# PWM.net
KiCad netlist of a schematic drawn in Altium Designer
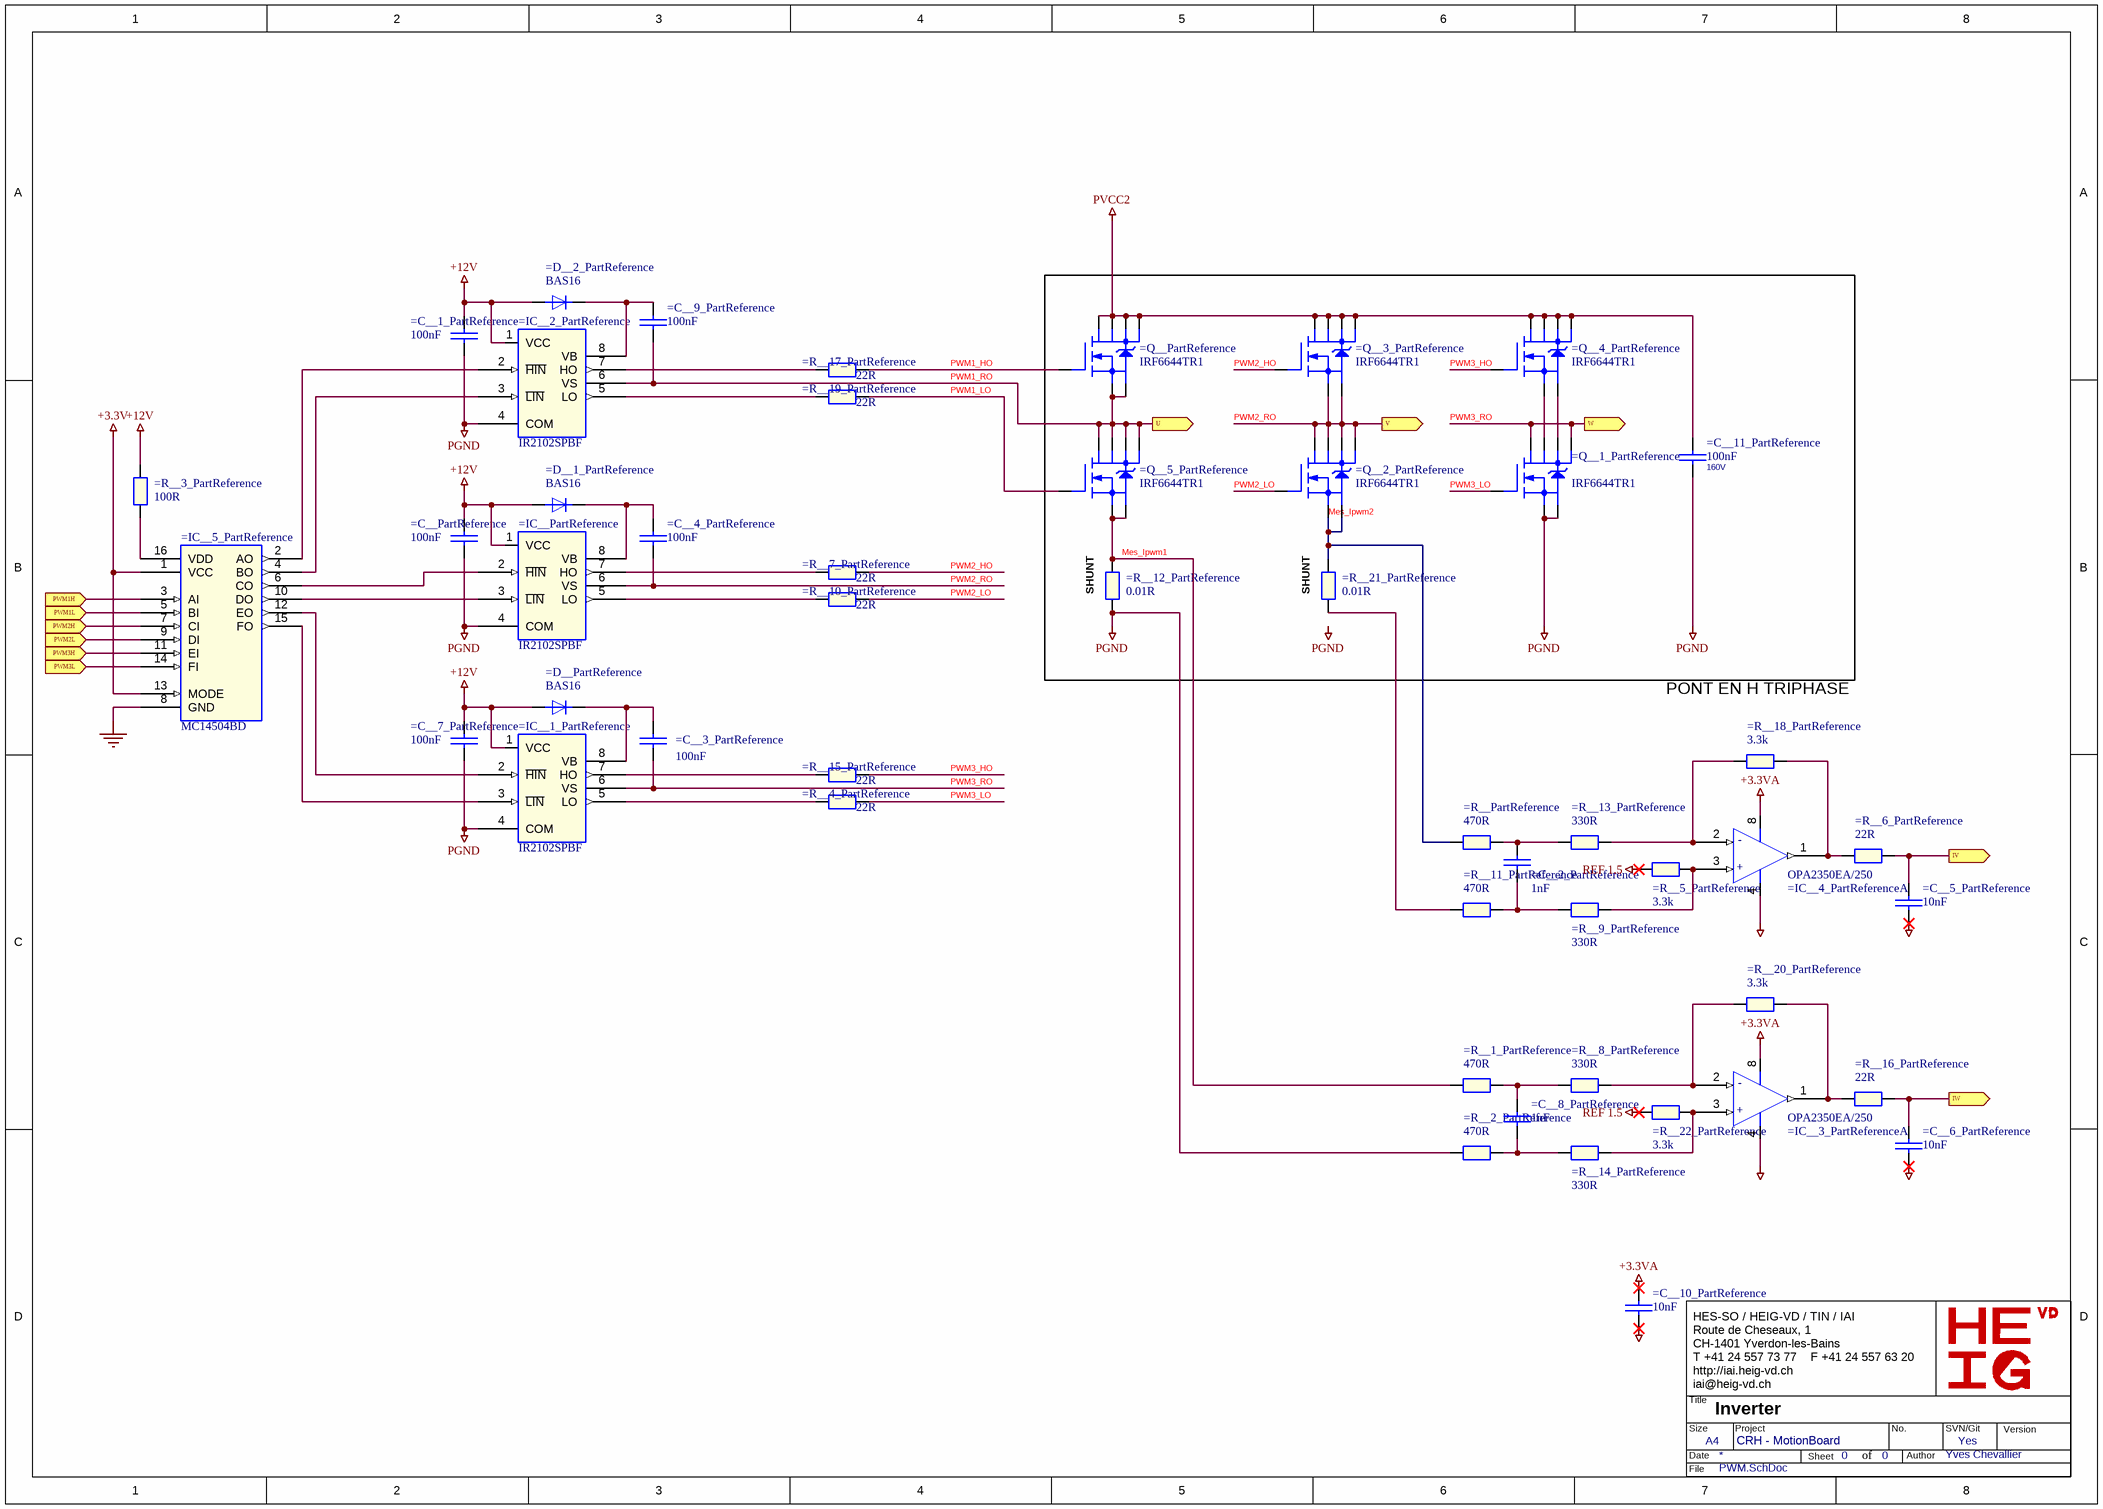
[diagram p0: PWM.SchDoc]

(export (version "E")
  (design (tool "Eeschema 10.0.6"))
  (components
    (comp (ref "=C__1_PartReference")
      (value "100nF")
      (footprint "SM/C_0805")
      (libsource (lib "*") (part "C_Dup1"))
    )
    (comp (ref "=C__2_PartReference")
      (value "1nF")
      (footprint "SM/C_0805")
      (libsource (lib "*") (part "C_Dup1"))
    )
    (comp (ref "=C__3_PartReference")
      (value "100nF")
      (footprint "SM/C_0805")
      (libsource (lib "*") (part "C_Dup1"))
    )
    (comp (ref "=C__4_PartReference")
      (value "100nF")
      (footprint "SM/C_0805")
      (libsource (lib "*") (part "C_Dup1"))
    )
    (comp (ref "=C__5_PartReference")
      (value "10nF")
      (footprint "SM/C_0805")
      (libsource (lib "*") (part "C_Dup1"))
    )
    (comp (ref "=C__6_PartReference")
      (value "10nF")
      (footprint "SM/C_0805")
      (libsource (lib "*") (part "C_Dup1"))
    )
    (comp (ref "=C__7_PartReference")
      (value "100nF")
      (footprint "SM/C_0805")
      (libsource (lib "*") (part "C_Dup1"))
    )
    (comp (ref "=C__8_PartReference")
      (value "1nF")
      (footprint "SM/C_0805")
      (libsource (lib "*") (part "C_Dup1"))
    )
    (comp (ref "=C__9_PartReference")
      (value "100nF")
      (footprint "SM/C_0805")
      (libsource (lib "*") (part "C_Dup1"))
    )
    (comp (ref "=C__10_PartReference")
      (value "10nF")
      (footprint "SM/C_0805")
      (libsource (lib "*") (part "C_Dup1"))
    )
    (comp (ref "=C__11_PartReference")
      (value "100nF")
      (footprint "SM/C_0805")
      (fields (field (name "VOLTAGE") "160V"))
      (libsource (lib "*") (part "C_Dup1"))
    )
    (comp (ref "=C__PartReference")
      (value "100nF")
      (footprint "SM/C_0805")
      (libsource (lib "*") (part "C_Dup1"))
    )
    (comp (ref "=D__1_PartReference")
      (value "BAS16")
      (footprint "HEIG/SM/SOT23")
      (fields (field (name "VOLTAGE") "85V"))
      (libsource (lib "*") (part "D_2"))
    )
    (comp (ref "=D__2_PartReference")
      (value "BAS16")
      (footprint "HEIG/SM/SOT23")
      (fields (field (name "VOLTAGE") "85V"))
      (libsource (lib "*") (part "D_4"))
    )
    (comp (ref "=D__PartReference")
      (value "BAS16")
      (footprint "HEIG/SM/SOT23")
      (fields (field (name "VOLTAGE") "85V"))
      (libsource (lib "*") (part "D_3"))
    )
    (comp (ref "=IC__1_PartReference")
      (value "IR2102SPBF")
      (footprint "SOG.050/8/WG.244/L.200")
      (libsource (lib "*") (part "IR2102/SO_0"))
    )
    (comp (ref "=IC__2_PartReference")
      (value "IR2102SPBF")
      (footprint "SOG.050/8/WG.244/L.200")
      (libsource (lib "*") (part "IR2102/SO_0"))
    )
    (comp (ref "=IC__3_PartReference")
      (value "OPA2350EA/250")
      (footprint "HEIG/SM/MSOP8")
      (libsource (lib "*") (part "OPA2340_2"))
    )
    (comp (ref "=IC__4_PartReference")
      (value "OPA2350EA/250")
      (footprint "HEIG/SM/MSOP8")
      (libsource (lib "*") (part "OPA2340_2"))
    )
    (comp (ref "=IC__5_PartReference")
      (value "MC14504BD")
      (footprint "SOG.050/16/WG.244/L.400")
      (libsource (lib "*") (part "CD4504BMS_1"))
    )
    (comp (ref "=IC__PartReference")
      (value "IR2102SPBF")
      (footprint "SOG.050/8/WG.244/L.200")
      (libsource (lib "*") (part "IR2102/SO_0_Dup1"))
    )
    (comp (ref "=Q__1_PartReference")
      (value "IRF6644TR1")
      (footprint "HEIG/DIRECTFET/MN")
      (libsource (lib "*") (part "IRF3710S/SM_0"))
    )
    (comp (ref "=Q__2_PartReference")
      (value "IRF6644TR1")
      (footprint "HEIG/DIRECTFET/MN")
      (libsource (lib "*") (part "IRF3710S/SM_0"))
    )
    (comp (ref "=Q__3_PartReference")
      (value "IRF6644TR1")
      (footprint "HEIG/DIRECTFET/MN")
      (libsource (lib "*") (part "IRF3710S/SM_0"))
    )
    (comp (ref "=Q__4_PartReference")
      (value "IRF6644TR1")
      (footprint "HEIG/DIRECTFET/MN")
      (libsource (lib "*") (part "IRF3710S/SM_0"))
    )
    (comp (ref "=Q__5_PartReference")
      (value "IRF6644TR1")
      (footprint "HEIG/DIRECTFET/MN")
      (libsource (lib "*") (part "IRF3710S/SM_0"))
    )
    (comp (ref "=Q__PartReference")
      (value "IRF6644TR1")
      (footprint "HEIG/DIRECTFET/MN")
      (libsource (lib "*") (part "IRF3710S/SM_0"))
    )
    (comp (ref "=R__1_PartReference") (value "470R") (footprint "R400") (libsource (lib "*") (part "R_Dup1")))
    (comp (ref "=R__2_PartReference") (value "470R") (footprint "R400") (libsource (lib "*") (part "R_Dup1")))
    (comp (ref "=R__3_PartReference")
      (value "100R")
      (footprint "R400")
      (libsource (lib "") (part "R_Dup1_1"))
    )
    (comp (ref "=R__4_PartReference") (value "22R") (footprint "R400") (libsource (lib "*") (part "R_Dup1")))
    (comp (ref "=R__5_PartReference") (value "3.3k") (footprint "R400") (libsource (lib "*") (part "R_Dup1")))
    (comp (ref "=R__6_PartReference") (value "22R") (footprint "R400") (libsource (lib "*") (part "R_Dup1")))
    (comp (ref "=R__7_PartReference") (value "22R") (footprint "R400") (libsource (lib "*") (part "R_Dup1")))
    (comp (ref "=R__8_PartReference") (value "330R") (footprint "R400") (libsource (lib "*") (part "R_Dup1")))
    (comp (ref "=R__9_PartReference") (value "330R") (footprint "R400") (libsource (lib "*") (part "R_Dup1")))
    (comp (ref "=R__10_PartReference") (value "22R") (footprint "R400") (libsource (lib "*") (part "R_Dup1")))
    (comp (ref "=R__11_PartReference")
      (value "470R")
      (footprint "R400")
      (libsource (lib "*") (part "R_Dup1"))
    )
    (comp (ref "=R__12_PartReference")
      (value "0.01R")
      (footprint "R400")
      (fields (field (name "VOLTAGE") "200V"))
      (libsource (lib "") (part "R_Dup1_2"))
    )
    (comp (ref "=R__13_PartReference")
      (value "330R")
      (footprint "R400")
      (libsource (lib "*") (part "R_Dup1"))
    )
    (comp (ref "=R__14_PartReference")
      (value "330R")
      (footprint "R400")
      (libsource (lib "*") (part "R_Dup1"))
    )
    (comp (ref "=R__15_PartReference") (value "22R") (footprint "R400") (libsource (lib "*") (part "R_Dup1")))
    (comp (ref "=R__16_PartReference") (value "22R") (footprint "R400") (libsource (lib "*") (part "R_Dup1")))
    (comp (ref "=R__17_PartReference") (value "22R") (footprint "R400") (libsource (lib "*") (part "R_Dup1")))
    (comp (ref "=R__18_PartReference")
      (value "3.3k")
      (footprint "R400")
      (libsource (lib "*") (part "R_Dup1"))
    )
    (comp (ref "=R__19_PartReference") (value "22R") (footprint "R400") (libsource (lib "*") (part "R_Dup1")))
    (comp (ref "=R__20_PartReference")
      (value "3.3k")
      (footprint "R400")
      (libsource (lib "*") (part "R_Dup1"))
    )
    (comp (ref "=R__21_PartReference")
      (value "0.01R")
      (footprint "R400")
      (fields (field (name "VOLTAGE") "200V"))
      (libsource (lib "") (part "R_Dup1_2"))
    )
    (comp (ref "=R__22_PartReference")
      (value "3.3k")
      (footprint "R400")
      (libsource (lib "*") (part "R_Dup1"))
    )
    (comp (ref "=R__PartReference") (value "470R") (footprint "R400") (libsource (lib "*") (part "R_Dup1")))
  )
  (nets
    (net (code "1") (name "+3.3V") (class "Default")
      (node (ref "=IC__5_PartReference") (pin "1") (pinfunction "VCC_1") (pintype "power_in"))
      (node (ref "=IC__5_PartReference") (pin "13") (pinfunction "MODE_13") (pintype "input"))
    )
    (net (code "2") (name "+3.3VA") (class "Default")
      (node (ref "=C__10_PartReference") (pin "1") (pinfunction "1_1") (pintype "passive"))
      (node (ref "=IC__3_PartReference") (pin "8") (pinfunction "+VCC_8") (pintype "power_in"))
      (node (ref "=IC__4_PartReference") (pin "8") (pinfunction "+VCC_8") (pintype "power_in"))
    )
    (net (code "3") (name "+12V") (class "Default")
      (node (ref "=C__1_PartReference") (pin "1") (pinfunction "1_1") (pintype "passive"))
      (node (ref "=C__7_PartReference") (pin "1") (pinfunction "1_1") (pintype "passive"))
      (node (ref "=C__PartReference") (pin "1") (pinfunction "1_1") (pintype "passive"))
      (node (ref "=D__1_PartReference") (pin "1") (pinfunction "a_1") (pintype "passive"))
      (node (ref "=D__2_PartReference") (pin "1") (pinfunction "a_1") (pintype "passive"))
      (node (ref "=D__PartReference") (pin "1") (pinfunction "a_1") (pintype "passive"))
      (node (ref "=IC__1_PartReference") (pin "1") (pinfunction "VCC_1") (pintype "power_in"))
      (node (ref "=IC__2_PartReference") (pin "1") (pinfunction "VCC_1") (pintype "power_in"))
      (node (ref "=IC__PartReference") (pin "1") (pinfunction "VCC_1") (pintype "power_in"))
      (node (ref "=R__3_PartReference") (pin "2") (pinfunction "2_2") (pintype "passive"))
    )
    (net (code "4") (name "/IV") (class "Default")
      (node (ref "=C__5_PartReference") (pin "1") (pinfunction "1_1") (pintype "passive"))
      (node (ref "=R__6_PartReference") (pin "2") (pinfunction "2_2") (pintype "passive"))
    )
    (net (code "5") (name "/IW") (class "Default")
      (node (ref "=C__6_PartReference") (pin "1") (pinfunction "1_1") (pintype "passive"))
      (node (ref "=R__16_PartReference") (pin "2") (pinfunction "2_2") (pintype "passive"))
    )
    (net (code "6") (name "/Mes_Ipwm1") (class "Default")
      (node (ref "=Q__5_PartReference") (pin "S1") (pinfunction "S_S1") (pintype "passive"))
      (node (ref "=Q__5_PartReference") (pin "S2") (pinfunction "S_S2") (pintype "passive"))
      (node (ref "=R__12_PartReference") (pin "1") (pinfunction "1_1") (pintype "passive"))
      (node (ref "=R__1_PartReference") (pin "1") (pinfunction "1_1") (pintype "passive"))
    )
    (net (code "7") (name "/Mes_Ipwm2") (class "Default")
      (node (ref "=Q__2_PartReference") (pin "S1") (pinfunction "S_S1") (pintype "passive"))
      (node (ref "=Q__2_PartReference") (pin "S2") (pinfunction "S_S2") (pintype "passive"))
      (node (ref "=R__21_PartReference") (pin "1") (pinfunction "1_1") (pintype "passive"))
      (node (ref "=R__PartReference") (pin "1") (pinfunction "1_1") (pintype "passive"))
    )
    (net (code "8") (name "/PWM1H") (class "Default")
      (node (ref "=IC__5_PartReference") (pin "3") (pinfunction "AI_3") (pintype "input"))
    )
    (net (code "9") (name "/PWM1L") (class "Default")
      (node (ref "=IC__5_PartReference") (pin "5") (pinfunction "BI_5") (pintype "input"))
    )
    (net (code "10") (name "/PWM1_HO") (class "Default")
      (node (ref "=Q__PartReference") (pin "G") (pinfunction "G_G") (pintype "passive"))
      (node (ref "=R__17_PartReference") (pin "2") (pinfunction "2_2") (pintype "passive"))
    )
    (net (code "11") (name "/PWM1_LO") (class "Default")
      (node (ref "=Q__5_PartReference") (pin "G") (pinfunction "G_G") (pintype "passive"))
      (node (ref "=R__19_PartReference") (pin "2") (pinfunction "2_2") (pintype "passive"))
    )
    (net (code "12") (name "/PWM1_RO") (class "Default")
      (node (ref "=C__9_PartReference") (pin "2") (pinfunction "2_2") (pintype "passive"))
      (node (ref "=IC__2_PartReference") (pin "6") (pinfunction "VS_6") (pintype "passive"))
      (node (ref "=Q__5_PartReference") (pin "D1") (pinfunction "D_D1") (pintype "passive"))
      (node (ref "=Q__5_PartReference") (pin "D2") (pinfunction "D_D2") (pintype "passive"))
      (node (ref "=Q__5_PartReference") (pin "D3") (pinfunction "D_D3") (pintype "passive"))
      (node (ref "=Q__5_PartReference") (pin "D4") (pinfunction "D_D4") (pintype "passive"))
      (node (ref "=Q__PartReference") (pin "S1") (pinfunction "S_S1") (pintype "passive"))
      (node (ref "=Q__PartReference") (pin "S2") (pinfunction "S_S2") (pintype "passive"))
    )
    (net (code "13") (name "/PWM2H") (class "Default")
      (node (ref "=IC__5_PartReference") (pin "7") (pinfunction "CI_7") (pintype "input"))
    )
    (net (code "14") (name "/PWM2L") (class "Default")
      (node (ref "=IC__5_PartReference") (pin "9") (pinfunction "DI_9") (pintype "input"))
    )
    (net (code "15") (name "/PWM2_HO") (class "Default")
      (node (ref "=Q__3_PartReference") (pin "G") (pinfunction "G_G") (pintype "passive"))
      (node (ref "=R__7_PartReference") (pin "2") (pinfunction "2_2") (pintype "passive"))
    )
    (net (code "16") (name "/PWM2_LO") (class "Default")
      (node (ref "=Q__2_PartReference") (pin "G") (pinfunction "G_G") (pintype "passive"))
      (node (ref "=R__10_PartReference") (pin "2") (pinfunction "2_2") (pintype "passive"))
    )
    (net (code "17") (name "/PWM2_RO") (class "Default")
      (node (ref "=C__4_PartReference") (pin "2") (pinfunction "2_2") (pintype "passive"))
      (node (ref "=IC__PartReference") (pin "6") (pinfunction "VS_6") (pintype "passive"))
      (node (ref "=Q__2_PartReference") (pin "D1") (pinfunction "D_D1") (pintype "passive"))
      (node (ref "=Q__2_PartReference") (pin "D2") (pinfunction "D_D2") (pintype "passive"))
      (node (ref "=Q__2_PartReference") (pin "D3") (pinfunction "D_D3") (pintype "passive"))
      (node (ref "=Q__2_PartReference") (pin "D4") (pinfunction "D_D4") (pintype "passive"))
      (node (ref "=Q__3_PartReference") (pin "S1") (pinfunction "S_S1") (pintype "passive"))
      (node (ref "=Q__3_PartReference") (pin "S2") (pinfunction "S_S2") (pintype "passive"))
    )
    (net (code "18") (name "/PWM3H") (class "Default")
      (node (ref "=IC__5_PartReference") (pin "11") (pinfunction "EI_11") (pintype "input"))
    )
    (net (code "19") (name "/PWM3L") (class "Default")
      (node (ref "=IC__5_PartReference") (pin "14") (pinfunction "FI_14") (pintype "input"))
    )
    (net (code "20") (name "/PWM3_HO") (class "Default")
      (node (ref "=Q__4_PartReference") (pin "G") (pinfunction "G_G") (pintype "passive"))
      (node (ref "=R__15_PartReference") (pin "2") (pinfunction "2_2") (pintype "passive"))
    )
    (net (code "21") (name "/PWM3_LO") (class "Default")
      (node (ref "=Q__1_PartReference") (pin "G") (pinfunction "G_G") (pintype "passive"))
      (node (ref "=R__4_PartReference") (pin "2") (pinfunction "2_2") (pintype "passive"))
    )
    (net (code "22") (name "/PWM3_RO") (class "Default")
      (node (ref "=C__3_PartReference") (pin "2") (pinfunction "2_2") (pintype "passive"))
      (node (ref "=IC__1_PartReference") (pin "6") (pinfunction "VS_6") (pintype "passive"))
      (node (ref "=Q__1_PartReference") (pin "D3") (pinfunction "D_D3") (pintype "passive"))
      (node (ref "=Q__1_PartReference") (pin "D4") (pinfunction "D_D4") (pintype "passive"))
    )
    (net (code "23") (name "AGND") (class "Default")
      (node (ref "=C__10_PartReference") (pin "2") (pinfunction "2_2") (pintype "passive"))
      (node (ref "=C__5_PartReference") (pin "2") (pinfunction "2_2") (pintype "passive"))
      (node (ref "=C__6_PartReference") (pin "2") (pinfunction "2_2") (pintype "passive"))
      (node (ref "=IC__3_PartReference") (pin "4") (pinfunction "-VCC_4") (pintype "power_in"))
      (node (ref "=IC__4_PartReference") (pin "4") (pinfunction "-VCC_4") (pintype "power_in"))
    )
    (net (code "24") (name "GND") (class "Default")
      (node (ref "=IC__5_PartReference") (pin "8") (pinfunction "GND_8") (pintype "power_in"))
    )
    (net (code "25") (name "Net-(=C__2_PartReference-Pad1)") (class "Default")
      (node (ref "=C__2_PartReference") (pin "1") (pinfunction "1_1") (pintype "passive"))
      (node (ref "=R__13_PartReference") (pin "1") (pinfunction "1_1") (pintype "passive"))
      (node (ref "=R__PartReference") (pin "2") (pinfunction "2_2") (pintype "passive"))
    )
    (net (code "26") (name "Net-(=C__2_PartReference-Pad2)") (class "Default")
      (node (ref "=C__2_PartReference") (pin "2") (pinfunction "2_2") (pintype "passive"))
      (node (ref "=R__11_PartReference") (pin "2") (pinfunction "2_2") (pintype "passive"))
      (node (ref "=R__9_PartReference") (pin "1") (pinfunction "1_1") (pintype "passive"))
    )
    (net (code "27") (name "Net-(=C__8_PartReference-Pad1)") (class "Default")
      (node (ref "=C__8_PartReference") (pin "1") (pinfunction "1_1") (pintype "passive"))
      (node (ref "=R__1_PartReference") (pin "2") (pinfunction "2_2") (pintype "passive"))
      (node (ref "=R__8_PartReference") (pin "1") (pinfunction "1_1") (pintype "passive"))
    )
    (net (code "28") (name "Net-(=C__8_PartReference-Pad2)") (class "Default")
      (node (ref "=C__8_PartReference") (pin "2") (pinfunction "2_2") (pintype "passive"))
      (node (ref "=R__14_PartReference") (pin "1") (pinfunction "1_1") (pintype "passive"))
      (node (ref "=R__2_PartReference") (pin "2") (pinfunction "2_2") (pintype "passive"))
    )
    (net (code "29") (name "Net-(=D__1_PartReference-k)") (class "Default")
      (node (ref "=C__4_PartReference") (pin "1") (pinfunction "1_1") (pintype "passive"))
      (node (ref "=D__1_PartReference") (pin "3") (pinfunction "k_3") (pintype "passive"))
      (node (ref "=IC__PartReference") (pin "8") (pinfunction "VB_8") (pintype "power_in"))
    )
    (net (code "30") (name "Net-(=D__2_PartReference-k)") (class "Default")
      (node (ref "=C__9_PartReference") (pin "1") (pinfunction "1_1") (pintype "passive"))
      (node (ref "=D__2_PartReference") (pin "3") (pinfunction "k_3") (pintype "passive"))
      (node (ref "=IC__2_PartReference") (pin "8") (pinfunction "VB_8") (pintype "power_in"))
    )
    (net (code "31") (name "Net-(=D__PartReference-k)") (class "Default")
      (node (ref "=C__3_PartReference") (pin "1") (pinfunction "1_1") (pintype "passive"))
      (node (ref "=D__PartReference") (pin "3") (pinfunction "k_3") (pintype "passive"))
      (node (ref "=IC__1_PartReference") (pin "8") (pinfunction "VB_8") (pintype "power_in"))
    )
    (net (code "32") (name "Net-(=IC__1_PartReference-HO)") (class "Default")
      (node (ref "=IC__1_PartReference") (pin "7") (pinfunction "HO_7") (pintype "output"))
      (node (ref "=R__15_PartReference") (pin "1") (pinfunction "1_1") (pintype "passive"))
    )
    (net (code "33") (name "Net-(=IC__1_PartReference-LO)") (class "Default")
      (node (ref "=IC__1_PartReference") (pin "5") (pinfunction "LO_5") (pintype "output"))
      (node (ref "=R__4_PartReference") (pin "1") (pinfunction "1_1") (pintype "passive"))
    )
    (net (code "34") (name "Net-(=IC__1_PartReference-~{HIN})") (class "Default")
      (node (ref "=IC__1_PartReference") (pin "2") (pinfunction "~{HIN}_2") (pintype "input"))
      (node (ref "=IC__5_PartReference") (pin "12") (pinfunction "EO_12") (pintype "output"))
    )
    (net (code "35") (name "Net-(=IC__1_PartReference-~{LIN})") (class "Default")
      (node (ref "=IC__1_PartReference") (pin "3") (pinfunction "~{LIN}_3") (pintype "input"))
      (node (ref "=IC__5_PartReference") (pin "15") (pinfunction "FO_15") (pintype "output"))
    )
    (net (code "36") (name "Net-(=IC__2_PartReference-HO)") (class "Default")
      (node (ref "=IC__2_PartReference") (pin "7") (pinfunction "HO_7") (pintype "output"))
      (node (ref "=R__17_PartReference") (pin "1") (pinfunction "1_1") (pintype "passive"))
    )
    (net (code "37") (name "Net-(=IC__2_PartReference-LO)") (class "Default")
      (node (ref "=IC__2_PartReference") (pin "5") (pinfunction "LO_5") (pintype "output"))
      (node (ref "=R__19_PartReference") (pin "1") (pinfunction "1_1") (pintype "passive"))
    )
    (net (code "38") (name "Net-(=IC__2_PartReference-~{HIN})") (class "Default")
      (node (ref "=IC__2_PartReference") (pin "2") (pinfunction "~{HIN}_2") (pintype "input"))
      (node (ref "=IC__5_PartReference") (pin "2") (pinfunction "AO_2") (pintype "output"))
    )
    (net (code "39") (name "Net-(=IC__2_PartReference-~{LIN})") (class "Default")
      (node (ref "=IC__2_PartReference") (pin "3") (pinfunction "~{LIN}_3") (pintype "input"))
      (node (ref "=IC__5_PartReference") (pin "4") (pinfunction "BO_4") (pintype "output"))
    )
    (net (code "40") (name "Net-(=IC__3_PartReferenceA-+IN)") (class "Default")
      (node (ref "=IC__3_PartReference") (pin "3") (pinfunction "+IN_3") (pintype "input"))
      (node (ref "=R__14_PartReference") (pin "2") (pinfunction "2_2") (pintype "passive"))
      (node (ref "=R__22_PartReference") (pin "2") (pinfunction "2_2") (pintype "passive"))
    )
    (net (code "41") (name "Net-(=IC__3_PartReferenceA--IN)") (class "Default")
      (node (ref "=IC__3_PartReference") (pin "2") (pinfunction "-IN_2") (pintype "input"))
      (node (ref "=R__20_PartReference") (pin "1") (pinfunction "1_1") (pintype "passive"))
      (node (ref "=R__8_PartReference") (pin "2") (pinfunction "2_2") (pintype "passive"))
    )
    (net (code "42") (name "Net-(=IC__3_PartReferenceA-OUT)") (class "Default")
      (node (ref "=IC__3_PartReference") (pin "1") (pinfunction "OUT_1") (pintype "output"))
      (node (ref "=R__16_PartReference") (pin "1") (pinfunction "1_1") (pintype "passive"))
      (node (ref "=R__20_PartReference") (pin "2") (pinfunction "2_2") (pintype "passive"))
    )
    (net (code "43") (name "Net-(=IC__4_PartReferenceA-+IN)") (class "Default")
      (node (ref "=IC__4_PartReference") (pin "3") (pinfunction "+IN_3") (pintype "input"))
      (node (ref "=R__5_PartReference") (pin "2") (pinfunction "2_2") (pintype "passive"))
      (node (ref "=R__9_PartReference") (pin "2") (pinfunction "2_2") (pintype "passive"))
    )
    (net (code "44") (name "Net-(=IC__4_PartReferenceA--IN)") (class "Default")
      (node (ref "=IC__4_PartReference") (pin "2") (pinfunction "-IN_2") (pintype "input"))
      (node (ref "=R__13_PartReference") (pin "2") (pinfunction "2_2") (pintype "passive"))
      (node (ref "=R__18_PartReference") (pin "1") (pinfunction "1_1") (pintype "passive"))
    )
    (net (code "45") (name "Net-(=IC__4_PartReferenceA-OUT)") (class "Default")
      (node (ref "=IC__4_PartReference") (pin "1") (pinfunction "OUT_1") (pintype "output"))
      (node (ref "=R__18_PartReference") (pin "2") (pinfunction "2_2") (pintype "passive"))
      (node (ref "=R__6_PartReference") (pin "1") (pinfunction "1_1") (pintype "passive"))
    )
    (net (code "46") (name "Net-(=IC__5_PartReference-CO)") (class "Default")
      (node (ref "=IC__5_PartReference") (pin "6") (pinfunction "CO_6") (pintype "output"))
      (node (ref "=IC__PartReference") (pin "2") (pinfunction "~{HIN}_2") (pintype "input"))
    )
    (net (code "47") (name "Net-(=IC__5_PartReference-DO)") (class "Default")
      (node (ref "=IC__5_PartReference") (pin "10") (pinfunction "DO_10") (pintype "output"))
      (node (ref "=IC__PartReference") (pin "3") (pinfunction "~{LIN}_3") (pintype "input"))
    )
    (net (code "48") (name "Net-(=IC__5_PartReference-VDD)") (class "Default")
      (node (ref "=IC__5_PartReference") (pin "16") (pinfunction "VDD_16") (pintype "power_in"))
      (node (ref "=R__3_PartReference") (pin "1") (pinfunction "1_1") (pintype "passive"))
    )
    (net (code "49") (name "Net-(=IC__PartReference-HO)") (class "Default")
      (node (ref "=IC__PartReference") (pin "7") (pinfunction "HO_7") (pintype "output"))
      (node (ref "=R__7_PartReference") (pin "1") (pinfunction "1_1") (pintype "passive"))
    )
    (net (code "50") (name "Net-(=IC__PartReference-LO)") (class "Default")
      (node (ref "=IC__PartReference") (pin "5") (pinfunction "LO_5") (pintype "output"))
      (node (ref "=R__10_PartReference") (pin "1") (pinfunction "1_1") (pintype "passive"))
    )
    (net (code "51") (name "Net-(=Q__1_PartReference-D-PadD1)") (class "Default")
      (node (ref "=Q__1_PartReference") (pin "D1") (pinfunction "D_D1") (pintype "passive"))
      (node (ref "=Q__4_PartReference") (pin "S1") (pinfunction "S_S1") (pintype "passive"))
    )
    (net (code "52") (name "Net-(=Q__1_PartReference-D-PadD2)") (class "Default")
      (node (ref "=Q__1_PartReference") (pin "D2") (pinfunction "D_D2") (pintype "passive"))
      (node (ref "=Q__4_PartReference") (pin "S2") (pinfunction "S_S2") (pintype "passive"))
    )
    (net (code "53") (name "Net-(=R__11_PartReference-Pad1)") (class "Default")
      (node (ref "=R__11_PartReference") (pin "1") (pinfunction "1_1") (pintype "passive"))
      (node (ref "=R__21_PartReference") (pin "2") (pinfunction "2_2") (pintype "passive"))
    )
    (net (code "54") (name "PGND") (class "Default")
      (node (ref "=C__11_PartReference") (pin "2") (pinfunction "2_2") (pintype "passive"))
      (node (ref "=C__1_PartReference") (pin "2") (pinfunction "2_2") (pintype "passive"))
      (node (ref "=C__7_PartReference") (pin "2") (pinfunction "2_2") (pintype "passive"))
      (node (ref "=C__PartReference") (pin "2") (pinfunction "2_2") (pintype "passive"))
      (node (ref "=IC__1_PartReference") (pin "4") (pinfunction "COM_4") (pintype "power_in"))
      (node (ref "=IC__2_PartReference") (pin "4") (pinfunction "COM_4") (pintype "power_in"))
      (node (ref "=IC__PartReference") (pin "4") (pinfunction "COM_4") (pintype "power_in"))
      (node (ref "=Q__1_PartReference") (pin "S1") (pinfunction "S_S1") (pintype "passive"))
      (node (ref "=Q__1_PartReference") (pin "S2") (pinfunction "S_S2") (pintype "passive"))
      (node (ref "=R__12_PartReference") (pin "2") (pinfunction "2_2") (pintype "passive"))
      (node (ref "=R__2_PartReference") (pin "1") (pinfunction "1_1") (pintype "passive"))
    )
    (net (code "55") (name "PVCC2") (class "Default")
      (node (ref "=C__11_PartReference") (pin "1") (pinfunction "1_1") (pintype "passive"))
      (node (ref "=Q__3_PartReference") (pin "D1") (pinfunction "D_D1") (pintype "passive"))
      (node (ref "=Q__3_PartReference") (pin "D2") (pinfunction "D_D2") (pintype "passive"))
      (node (ref "=Q__3_PartReference") (pin "D3") (pinfunction "D_D3") (pintype "passive"))
      (node (ref "=Q__3_PartReference") (pin "D4") (pinfunction "D_D4") (pintype "passive"))
      (node (ref "=Q__4_PartReference") (pin "D1") (pinfunction "D_D1") (pintype "passive"))
      (node (ref "=Q__4_PartReference") (pin "D2") (pinfunction "D_D2") (pintype "passive"))
      (node (ref "=Q__4_PartReference") (pin "D3") (pinfunction "D_D3") (pintype "passive"))
      (node (ref "=Q__4_PartReference") (pin "D4") (pinfunction "D_D4") (pintype "passive"))
      (node (ref "=Q__PartReference") (pin "D1") (pinfunction "D_D1") (pintype "passive"))
      (node (ref "=Q__PartReference") (pin "D2") (pinfunction "D_D2") (pintype "passive"))
      (node (ref "=Q__PartReference") (pin "D3") (pinfunction "D_D3") (pintype "passive"))
      (node (ref "=Q__PartReference") (pin "D4") (pinfunction "D_D4") (pintype "passive"))
    )
    (net (code "56") (name "REF 1.5") (class "Default")
      (node (ref "=R__22_PartReference") (pin "1") (pinfunction "1_1") (pintype "passive"))
      (node (ref "=R__5_PartReference") (pin "1") (pinfunction "1_1") (pintype "passive"))
    )
  )
)
